# THM_Block.net
KiCad netlist of a schematic drawn in Altium Designer
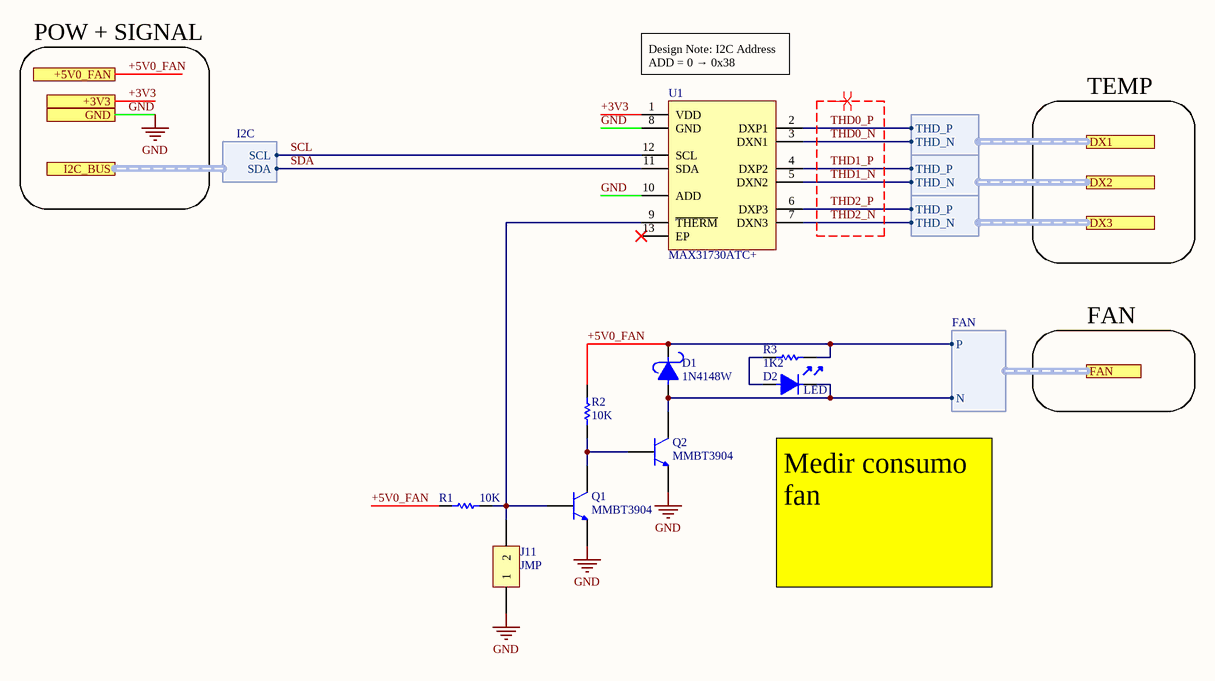
[diagram p0: THM_Block.SchDoc]

(export (version "E")
  (design (tool "Eeschema 10.0.6"))
  (components
    (comp (ref "D1")
      (value "1N4148W")
      (footprint "SOD-123")
      (description "100V 500mW Single 1.25V@150mA 4ns 150mA SOD-123  Switching Diode")
      (fields (field (name "JLCPART") "C2099"))
      (libsource (lib "LIB2022 - Semiconductors") (part "1N4148W"))
    )
    (comp (ref "D2")
      (value "LED")
      (footprint "LED-0805")
      (fields (field (name "JLCPART") "C84256"))
      (libsource (lib "LIB2022 - Optoelectronics") (part "LED-SMD"))
    )
    (comp (ref "J11")
      (value "JMP")
      (footprint "SIP1X2")
      (libsource (lib "LIB2022 - Connectors") (part "CON1X2"))
    )
    (comp (ref "Q1")
      (value "MMBT3904")
      (footprint "VS-SOT-23")
      (description "Bipolar (BJT) Transistor NPN 40 V 200 mA 300MHz 350 mW Surface Mount SOT-23")
      (fields (field (name "JLCPART") "C20526"))
      (libsource (lib "LIB2022 - Semiconductors") (part "MMBT3904"))
    )
    (comp (ref "Q2")
      (value "MMBT3904")
      (footprint "VS-SOT-23")
      (description "Bipolar (BJT) Transistor NPN 40 V 200 mA 300MHz 350 mW Surface Mount SOT-23")
      (fields (field (name "JLCPART") "C20526"))
      (libsource (lib "LIB2022 - Semiconductors") (part "MMBT3904"))
    )
    (comp (ref "R1")
      (value "10K")
      (footprint "0402-RES-PANASONIC")
      (fields (field (name "JLCPART") "C25744"))
      (libsource (lib "LIB2022 - Passives") (part "RES-SMD"))
    )
    (comp (ref "R2")
      (value "10K")
      (footprint "0402-RES-PANASONIC")
      (fields (field (name "JLCPART") "C25744"))
      (libsource (lib "LIB2022 - Passives") (part "RES-SMD"))
    )
    (comp (ref "R3")
      (value "1K2")
      (footprint "0402-RES-PANASONIC")
      (fields (field (name "JLCPART") "C25862"))
      (libsource (lib "LIB2022 - Passives") (part "RES-SMD"))
    )
    (comp (ref "U1")
      (value "MAX31730ATC+")
      (footprint "MAX31730ATC+")
      (description "Temperature Sensor Digital, Local/Remote 11 b 12-TDFN (3x3)")
      (libsource (lib "LIB2022 - ICs") (part "MAX31730ATC+"))
    )
  )
  (nets
    (net (code "4") (name "/+3V3") (class "Default")
      (node (ref "U1") (pin "1") (pinfunction "VDD_1") (pintype "passive"))
    )
    (net (code "5") (name "/+5V0_FAN") (class "Default")
      (node (ref "D1") (pin "2") (pinfunction "2_2") (pintype "passive"))
      (node (ref "R1") (pin "2") (pinfunction "2_2") (pintype "passive"))
      (node (ref "R2") (pin "1") (pinfunction "1_1") (pintype "passive"))
      (node (ref "R3") (pin "2") (pinfunction "2_2") (pintype "passive"))
    )
    (net (code "6") (name "/SCL") (class "Default")
      (node (ref "U1") (pin "12") (pinfunction "SCL_12") (pintype "passive"))
    )
    (net (code "7") (name "/SDA") (class "Default")
      (node (ref "U1") (pin "11") (pinfunction "SDA_11") (pintype "passive"))
    )
    (net (code "8") (name "/THD0_N") (class "Default")
      (node (ref "U1") (pin "3") (pinfunction "DXN1_3") (pintype "passive"))
    )
    (net (code "9") (name "/THD0_P") (class "Default")
      (node (ref "U1") (pin "2") (pinfunction "DXP1_2") (pintype "passive"))
    )
    (net (code "10") (name "/THD1_N") (class "Default")
      (node (ref "U1") (pin "5") (pinfunction "DXN2_5") (pintype "passive"))
    )
    (net (code "11") (name "/THD1_P") (class "Default")
      (node (ref "U1") (pin "4") (pinfunction "DXP2_4") (pintype "passive"))
    )
    (net (code "12") (name "/THD2_N") (class "Default")
      (node (ref "U1") (pin "7") (pinfunction "DXN3_7") (pintype "passive"))
    )
    (net (code "13") (name "/THD2_P") (class "Default")
      (node (ref "U1") (pin "6") (pinfunction "DXP3_6") (pintype "passive"))
    )
    (net (code "17") (name "GND") (class "Default")
      (node (ref "J11") (pin "1") (pinfunction "1_1") (pintype "passive"))
      (node (ref "Q1") (pin "2") (pinfunction "E_2") (pintype "passive"))
      (node (ref "Q2") (pin "2") (pinfunction "E_2") (pintype "passive"))
      (node (ref "U1") (pin "10") (pinfunction "ADD_10") (pintype "passive"))
      (node (ref "U1") (pin "8") (pinfunction "GND_8") (pintype "passive"))
    )
    (net (code "18") (name "Net-(D2-Pad1)") (class "Default")
      (node (ref "D2") (pin "1") (pinfunction "1_1") (pintype "passive"))
      (node (ref "R3") (pin "1") (pinfunction "1_1") (pintype "passive"))
    )
    (net (code "19") (name "Net-(Q1-B)") (class "Default")
      (node (ref "J11") (pin "2") (pinfunction "2_2") (pintype "passive"))
      (node (ref "Q1") (pin "1") (pinfunction "B_1") (pintype "passive"))
      (node (ref "R1") (pin "1") (pinfunction "1_1") (pintype "passive"))
      (node (ref "U1") (pin "9") (pinfunction "~{THERM}_9") (pintype "passive"))
    )
    (net (code "20") (name "Net-(Q1-C)") (class "Default")
      (node (ref "Q1") (pin "3") (pinfunction "C_3") (pintype "passive"))
      (node (ref "Q2") (pin "1") (pinfunction "B_1") (pintype "passive"))
      (node (ref "R2") (pin "2") (pinfunction "2_2") (pintype "passive"))
    )
    (net (code "21") (name "Net-(Q2-C)") (class "Default")
      (node (ref "D1") (pin "1") (pinfunction "1_1") (pintype "passive"))
      (node (ref "D2") (pin "2") (pinfunction "2_2") (pintype "passive"))
      (node (ref "Q2") (pin "3") (pinfunction "C_3") (pintype "passive"))
    )
    (net (code "22") (name "unconnected-(U1-EP-Pad13)") (class "Default")
      (node (ref "U1") (pin "13") (pinfunction "EP_13") (pintype "passive+no_connect"))
    )
  )
)
